# RTFM.net
KiCad netlist of a schematic drawn in EAGLE
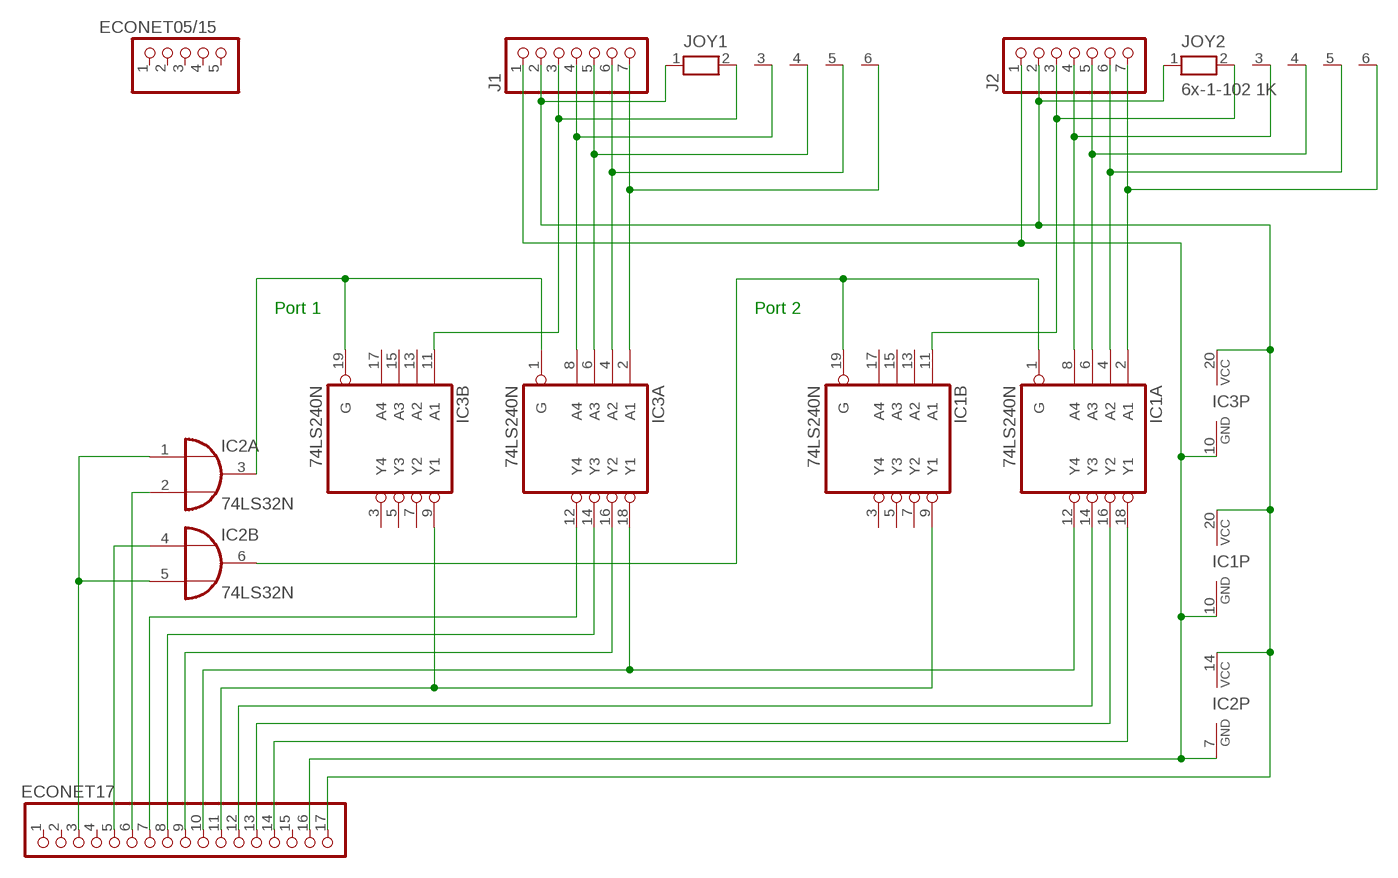
[diagram p0: schematic, sheet 1]

(export (version "E")
  (design (tool "Eeschema 10.0.6"))
  (components
    (comp (ref "ECONET05/15")
      (value "PINHD-1X5")
      (footprint "eagle-import:1X05")
      (libsource (lib "eagle-import") (part "PINHD-1X5"))
    )
    (comp (ref "ECONET17")
      (value "PINHD-1X17")
      (footprint "eagle-import:1X17")
      (libsource (lib "eagle-import") (part "PINHD-1X17"))
    )
    (comp (ref "IC1")
      (value "74LS240N")
      (footprint "eagle-import:DIL20")
      (libsource (lib "eagle-import") (part "74240NLS"))
    )
    (comp (ref "IC2")
      (value "74LS32N")
      (footprint "eagle-import:DIL14")
      (libsource (lib "eagle-import") (part "7432NLS"))
    )
    (comp (ref "IC3")
      (value "74LS240N")
      (footprint "eagle-import:DIL20")
      (libsource (lib "eagle-import") (part "74240NLS"))
    )
    (comp (ref "J1")
      (value "PINHD-1X7")
      (footprint "eagle-import:1X07")
      (libsource (lib "eagle-import") (part "PINHD-1X7"))
    )
    (comp (ref "J2")
      (value "PINHD-1X7")
      (footprint "eagle-import:1X07")
      (libsource (lib "eagle-import") (part "PINHD-1X7"))
    )
    (comp (ref "JOY1")
      (value "6x-1-102 1K")
      (footprint "eagle-import:RN-6")
      (libsource (lib "eagle-import") (part "RN05"))
    )
    (comp (ref "JOY2")
      (value "6x-1-102 1K")
      (footprint "eagle-import:RN-6")
      (libsource (lib "eagle-import") (part "RN05"))
    )
  )
  (nets
    (net (code "1") (name "Net-(IC1A-A1)") (class "Default")
      (node (ref "IC1") (pin "2") (pinfunction "A1_2") (pintype "input"))
      (node (ref "J2") (pin "7") (pinfunction "7_7") (pintype "passive"))
      (node (ref "JOY2") (pin "6") (pinfunction "6_6") (pintype "passive"))
    )
    (net (code "2") (name "Net-(IC1A-A2)") (class "Default")
      (node (ref "IC1") (pin "4") (pinfunction "A2_4") (pintype "input"))
      (node (ref "J2") (pin "6") (pinfunction "6_6") (pintype "passive"))
      (node (ref "JOY2") (pin "5") (pinfunction "5_5") (pintype "passive"))
    )
    (net (code "3") (name "Net-(IC1A-A3)") (class "Default")
      (node (ref "IC1") (pin "6") (pinfunction "A3_6") (pintype "input"))
      (node (ref "J2") (pin "5") (pinfunction "5_5") (pintype "passive"))
      (node (ref "JOY2") (pin "4") (pinfunction "4_4") (pintype "passive"))
    )
    (net (code "4") (name "Net-(IC1A-A4)") (class "Default")
      (node (ref "IC1") (pin "8") (pinfunction "A4_8") (pintype "input"))
      (node (ref "J2") (pin "4") (pinfunction "4_4") (pintype "passive"))
      (node (ref "JOY2") (pin "3") (pinfunction "3_3") (pintype "passive"))
    )
    (net (code "5") (name "Net-(IC1A-G)") (class "Default")
      (node (ref "IC1") (pin "1") (pinfunction "G_1") (pintype "input"))
      (node (ref "IC1") (pin "19") (pinfunction "G_19") (pintype "input"))
      (node (ref "IC2") (pin "6") (pinfunction "O_6") (pintype "output"))
    )
    (net (code "6") (name "Net-(IC1A-Y1)") (class "Default")
      (node (ref "ECONET17") (pin "14") (pinfunction "14_14") (pintype "passive"))
      (node (ref "IC1") (pin "18") (pinfunction "Y1_18") (pintype "tri_state"))
    )
    (net (code "7") (name "Net-(IC1A-Y2)") (class "Default")
      (node (ref "ECONET17") (pin "13") (pinfunction "13_13") (pintype "passive"))
      (node (ref "IC1") (pin "16") (pinfunction "Y2_16") (pintype "tri_state"))
    )
    (net (code "8") (name "Net-(IC1A-Y3)") (class "Default")
      (node (ref "ECONET17") (pin "12") (pinfunction "12_12") (pintype "passive"))
      (node (ref "IC1") (pin "14") (pinfunction "Y3_14") (pintype "tri_state"))
    )
    (net (code "9") (name "Net-(IC1A-Y4)") (class "Default")
      (node (ref "ECONET17") (pin "10") (pinfunction "10_10") (pintype "passive"))
      (node (ref "IC1") (pin "12") (pinfunction "Y4_12") (pintype "tri_state"))
      (node (ref "IC3") (pin "18") (pinfunction "Y1_18") (pintype "tri_state"))
    )
    (net (code "10") (name "Net-(IC1B-A1)") (class "Default")
      (node (ref "IC1") (pin "11") (pinfunction "A1_11") (pintype "input"))
      (node (ref "J2") (pin "3") (pinfunction "3_3") (pintype "passive"))
      (node (ref "JOY2") (pin "2") (pinfunction "2_2") (pintype "passive"))
    )
    (net (code "11") (name "Net-(IC1B-Y1)") (class "Default")
      (node (ref "ECONET17") (pin "11") (pinfunction "11_11") (pintype "passive"))
      (node (ref "IC1") (pin "9") (pinfunction "Y1_9") (pintype "tri_state"))
      (node (ref "IC3") (pin "9") (pinfunction "Y1_9") (pintype "tri_state"))
    )
    (net (code "12") (name "Net-(IC1C-GND)") (class "Default")
      (node (ref "ECONET17") (pin "16") (pinfunction "16_16") (pintype "passive"))
      (node (ref "IC1") (pin "10") (pinfunction "GND_10") (pintype "power_in"))
      (node (ref "IC2") (pin "7") (pinfunction "GND_7") (pintype "power_in"))
      (node (ref "IC3") (pin "10") (pinfunction "GND_10") (pintype "power_in"))
      (node (ref "J1") (pin "1") (pinfunction "1_1") (pintype "passive"))
      (node (ref "J2") (pin "1") (pinfunction "1_1") (pintype "passive"))
    )
    (net (code "13") (name "Net-(IC1C-VCC)") (class "Default")
      (node (ref "ECONET17") (pin "17") (pinfunction "17_17") (pintype "passive"))
      (node (ref "IC1") (pin "20") (pinfunction "VCC_20") (pintype "power_in"))
      (node (ref "IC2") (pin "14") (pinfunction "VCC_14") (pintype "power_in"))
      (node (ref "IC3") (pin "20") (pinfunction "VCC_20") (pintype "power_in"))
      (node (ref "J1") (pin "2") (pinfunction "2_2") (pintype "passive"))
      (node (ref "J2") (pin "2") (pinfunction "2_2") (pintype "passive"))
      (node (ref "JOY1") (pin "1") (pinfunction "1_1") (pintype "passive"))
      (node (ref "JOY2") (pin "1") (pinfunction "1_1") (pintype "passive"))
    )
    (net (code "14") (name "Net-(IC2A-I0)") (class "Default")
      (node (ref "ECONET17") (pin "3") (pinfunction "3_3") (pintype "passive"))
      (node (ref "IC2") (pin "1") (pinfunction "I0_1") (pintype "input"))
      (node (ref "IC2") (pin "5") (pinfunction "I1_5") (pintype "input"))
    )
    (net (code "15") (name "Net-(IC2A-I1)") (class "Default")
      (node (ref "ECONET17") (pin "6") (pinfunction "6_6") (pintype "passive"))
      (node (ref "IC2") (pin "2") (pinfunction "I1_2") (pintype "input"))
    )
    (net (code "16") (name "Net-(IC2A-O)") (class "Default")
      (node (ref "IC2") (pin "3") (pinfunction "O_3") (pintype "output"))
      (node (ref "IC3") (pin "1") (pinfunction "G_1") (pintype "input"))
      (node (ref "IC3") (pin "19") (pinfunction "G_19") (pintype "input"))
    )
    (net (code "17") (name "Net-(IC2B-I0)") (class "Default")
      (node (ref "ECONET17") (pin "5") (pinfunction "5_5") (pintype "passive"))
      (node (ref "IC2") (pin "4") (pinfunction "I0_4") (pintype "input"))
    )
    (net (code "18") (name "Net-(IC3A-A1)") (class "Default")
      (node (ref "IC3") (pin "2") (pinfunction "A1_2") (pintype "input"))
      (node (ref "J1") (pin "7") (pinfunction "7_7") (pintype "passive"))
      (node (ref "JOY1") (pin "6") (pinfunction "6_6") (pintype "passive"))
    )
    (net (code "19") (name "Net-(IC3A-A2)") (class "Default")
      (node (ref "IC3") (pin "4") (pinfunction "A2_4") (pintype "input"))
      (node (ref "J1") (pin "6") (pinfunction "6_6") (pintype "passive"))
      (node (ref "JOY1") (pin "5") (pinfunction "5_5") (pintype "passive"))
    )
    (net (code "20") (name "Net-(IC3A-A3)") (class "Default")
      (node (ref "IC3") (pin "6") (pinfunction "A3_6") (pintype "input"))
      (node (ref "J1") (pin "5") (pinfunction "5_5") (pintype "passive"))
      (node (ref "JOY1") (pin "4") (pinfunction "4_4") (pintype "passive"))
    )
    (net (code "21") (name "Net-(IC3A-A4)") (class "Default")
      (node (ref "IC3") (pin "8") (pinfunction "A4_8") (pintype "input"))
      (node (ref "J1") (pin "4") (pinfunction "4_4") (pintype "passive"))
      (node (ref "JOY1") (pin "3") (pinfunction "3_3") (pintype "passive"))
    )
    (net (code "22") (name "Net-(IC3A-Y2)") (class "Default")
      (node (ref "ECONET17") (pin "9") (pinfunction "9_9") (pintype "passive"))
      (node (ref "IC3") (pin "16") (pinfunction "Y2_16") (pintype "tri_state"))
    )
    (net (code "23") (name "Net-(IC3A-Y3)") (class "Default")
      (node (ref "ECONET17") (pin "8") (pinfunction "8_8") (pintype "passive"))
      (node (ref "IC3") (pin "14") (pinfunction "Y3_14") (pintype "tri_state"))
    )
    (net (code "24") (name "Net-(IC3A-Y4)") (class "Default")
      (node (ref "ECONET17") (pin "7") (pinfunction "7_7") (pintype "passive"))
      (node (ref "IC3") (pin "12") (pinfunction "Y4_12") (pintype "tri_state"))
    )
    (net (code "25") (name "Net-(IC3B-A1)") (class "Default")
      (node (ref "IC3") (pin "11") (pinfunction "A1_11") (pintype "input"))
      (node (ref "J1") (pin "3") (pinfunction "3_3") (pintype "passive"))
      (node (ref "JOY1") (pin "2") (pinfunction "2_2") (pintype "passive"))
    )
    (net (code "26") (name "unconnected-(ECONET05/15-Pad1)") (class "Default")
      (node (ref "ECONET05/15") (pin "1") (pinfunction "1_1") (pintype "passive"))
    )
    (net (code "27") (name "unconnected-(ECONET05/15-Pad2)") (class "Default")
      (node (ref "ECONET05/15") (pin "2") (pinfunction "2_2") (pintype "passive"))
    )
    (net (code "28") (name "unconnected-(ECONET05/15-Pad3)") (class "Default")
      (node (ref "ECONET05/15") (pin "3") (pinfunction "3_3") (pintype "passive"))
    )
    (net (code "29") (name "unconnected-(ECONET05/15-Pad4)") (class "Default")
      (node (ref "ECONET05/15") (pin "4") (pinfunction "4_4") (pintype "passive"))
    )
    (net (code "30") (name "unconnected-(ECONET05/15-Pad5)") (class "Default")
      (node (ref "ECONET05/15") (pin "5") (pinfunction "5_5") (pintype "passive"))
    )
    (net (code "31") (name "unconnected-(ECONET17-Pad1)") (class "Default")
      (node (ref "ECONET17") (pin "1") (pinfunction "1_1") (pintype "passive"))
    )
    (net (code "32") (name "unconnected-(ECONET17-Pad2)") (class "Default")
      (node (ref "ECONET17") (pin "2") (pinfunction "2_2") (pintype "passive"))
    )
    (net (code "33") (name "unconnected-(ECONET17-Pad4)") (class "Default")
      (node (ref "ECONET17") (pin "4") (pinfunction "4_4") (pintype "passive"))
    )
    (net (code "34") (name "unconnected-(ECONET17-Pad15)") (class "Default")
      (node (ref "ECONET17") (pin "15") (pinfunction "15_15") (pintype "passive"))
    )
    (net (code "35") (name "unconnected-(IC1B-A2-Pad13)") (class "Default")
      (node (ref "IC1") (pin "13") (pinfunction "A2_13") (pintype "input"))
    )
    (net (code "36") (name "unconnected-(IC1B-A3-Pad15)") (class "Default")
      (node (ref "IC1") (pin "15") (pinfunction "A3_15") (pintype "input"))
    )
    (net (code "37") (name "unconnected-(IC1B-A4-Pad17)") (class "Default")
      (node (ref "IC1") (pin "17") (pinfunction "A4_17") (pintype "input"))
    )
    (net (code "38") (name "unconnected-(IC1B-Y2-Pad7)") (class "Default")
      (node (ref "IC1") (pin "7") (pinfunction "Y2_7") (pintype "tri_state"))
    )
    (net (code "39") (name "unconnected-(IC1B-Y3-Pad5)") (class "Default")
      (node (ref "IC1") (pin "5") (pinfunction "Y3_5") (pintype "tri_state"))
    )
    (net (code "40") (name "unconnected-(IC1B-Y4-Pad3)") (class "Default")
      (node (ref "IC1") (pin "3") (pinfunction "Y4_3") (pintype "tri_state"))
    )
    (net (code "41") (name "unconnected-(IC3B-A2-Pad13)") (class "Default")
      (node (ref "IC3") (pin "13") (pinfunction "A2_13") (pintype "input"))
    )
    (net (code "42") (name "unconnected-(IC3B-A3-Pad15)") (class "Default")
      (node (ref "IC3") (pin "15") (pinfunction "A3_15") (pintype "input"))
    )
    (net (code "43") (name "unconnected-(IC3B-A4-Pad17)") (class "Default")
      (node (ref "IC3") (pin "17") (pinfunction "A4_17") (pintype "input"))
    )
    (net (code "44") (name "unconnected-(IC3B-Y2-Pad7)") (class "Default")
      (node (ref "IC3") (pin "7") (pinfunction "Y2_7") (pintype "tri_state"))
    )
    (net (code "45") (name "unconnected-(IC3B-Y3-Pad5)") (class "Default")
      (node (ref "IC3") (pin "5") (pinfunction "Y3_5") (pintype "tri_state"))
    )
    (net (code "46") (name "unconnected-(IC3B-Y4-Pad3)") (class "Default")
      (node (ref "IC3") (pin "3") (pinfunction "Y4_3") (pintype "tri_state"))
    )
  )
)
